# 04_BUZZER.net
KiCad netlist of a schematic drawn in Altium Designer
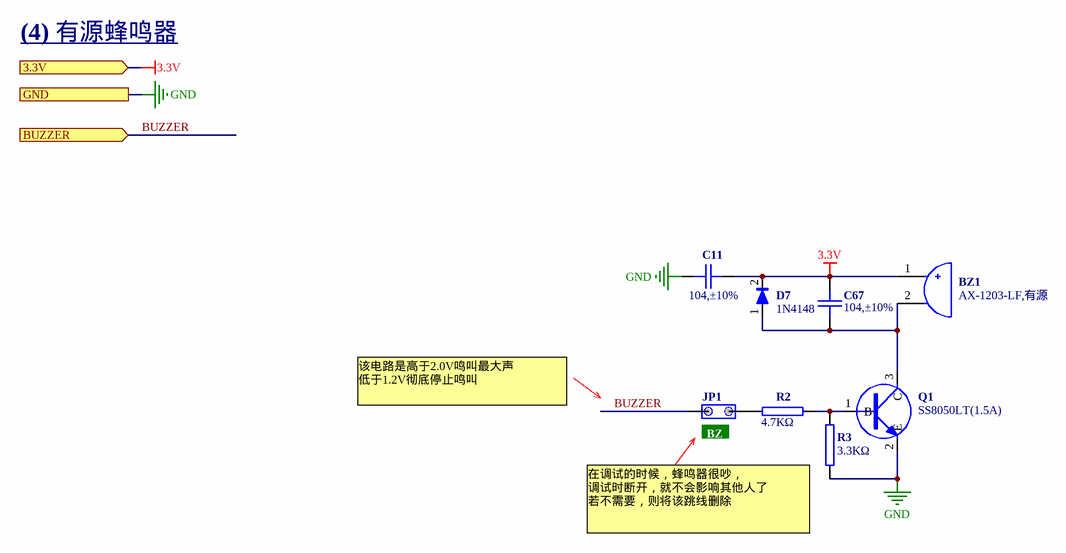
[diagram p0: 04. BUZZER.SchDoc]

(export (version "E")
  (design (tool "Eeschema 10.0.6"))
  (components
    (comp (ref "BZ1")
      (value "AX-1203-LF,有源")
      (footprint "BUZZ-.28/.46")
      (description "AX-1203-LF,有源,Φ12×7.5mm,,常州笠翔,RoHS")
      (fields (field (name "Comment") "BUZZER2"))
      (libsource (lib "ErpMaterialData") (part "BUZZER2"))
    )
    (comp (ref "C11")
      (value "104,±10%")
      (footprint "0603C")
      (description "104,±10%,50V,X7R,0603,*,RoHS")
      (libsource (lib "ErpMaterialData") (part "CAP1"))
    )
    (comp (ref "C67")
      (value "104,±10%")
      (footprint "0603C")
      (description "104,±10%,50V,X7R,0603,*,RoHS")
      (libsource (lib "ErpMaterialData") (part "CAP1"))
    )
    (comp (ref "D7")
      (value "1N4148")
      (footprint "SOD-323")
      (description "1N4148,SOD-323,RoHS")
      (fields (field (name "Comment") "DIODE1"))
      (libsource (lib "ErpMaterialData") (part "DIODE1"))
    )
    (comp (ref "JP1") (value "120Ω_EN") (footprint "sip-2") (libsource (lib "无需物料号元件") (part "JMP2")))
    (comp (ref "Q1")
      (value "SS8050LT(1.5A)")
      (footprint "SOT-23")
      (description "SS8050LT(1.5A),SOT-23,江苏长电,RoHS")
      (fields (field (name "Comment") "NPN-1"))
      (libsource (lib "ErpMaterialData") (part "NPN-1"))
    )
    (comp (ref "R2")
      (value "4.7KΩ")
      (footprint "0603R")
      (description "4.7KΩ,0603,*,RoHS")
      (libsource (lib "ErpMaterialData") (part "RES2"))
    )
    (comp (ref "R3")
      (value "3.3KΩ")
      (footprint "0603R")
      (description "3.3KΩ,0603,*,RoHS")
      (libsource (lib "ErpMaterialData") (part "RES2"))
    )
  )
  (nets
    (net (code "1") (name "/BUZZER") (class "Default")
      (node (ref "JP1") (pin "1") (pinfunction "1_1") (pintype "passive"))
    )
    (net (code "2") (name "3.3V") (class "Default")
      (node (ref "BZ1") (pin "1") (pinfunction "A_1") (pintype "passive"))
      (node (ref "C11") (pin "1") (pinfunction "1_1") (pintype "passive"))
      (node (ref "C67") (pin "2") (pinfunction "2_2") (pintype "passive"))
      (node (ref "D7") (pin "2") (pinfunction "2_2") (pintype "passive"))
    )
    (net (code "3") (name "GND") (class "Default")
      (node (ref "C11") (pin "2") (pinfunction "2_2") (pintype "passive"))
      (node (ref "Q1") (pin "2") (pinfunction "E_2") (pintype "passive"))
      (node (ref "R3") (pin "1") (pinfunction "1_1") (pintype "passive"))
    )
    (net (code "4") (name "Net-(BZ1-B)") (class "Default")
      (node (ref "BZ1") (pin "2") (pinfunction "B_2") (pintype "passive"))
      (node (ref "C67") (pin "1") (pinfunction "1_1") (pintype "passive"))
      (node (ref "D7") (pin "1") (pinfunction "1_1") (pintype "passive"))
      (node (ref "Q1") (pin "3") (pinfunction "C_3") (pintype "passive"))
    )
    (net (code "5") (name "Net-(JP1-Pad2)") (class "Default")
      (node (ref "JP1") (pin "2") (pinfunction "2_2") (pintype "passive"))
      (node (ref "R2") (pin "1") (pinfunction "1_1") (pintype "passive"))
    )
    (net (code "6") (name "Net-(Q1-B)") (class "Default")
      (node (ref "Q1") (pin "1") (pinfunction "B_1") (pintype "passive"))
      (node (ref "R2") (pin "2") (pinfunction "2_2") (pintype "passive"))
      (node (ref "R3") (pin "2") (pinfunction "2_2") (pintype "passive"))
    )
  )
)
